# tfsasi.net
KiCad netlist of a schematic drawn in EAGLE
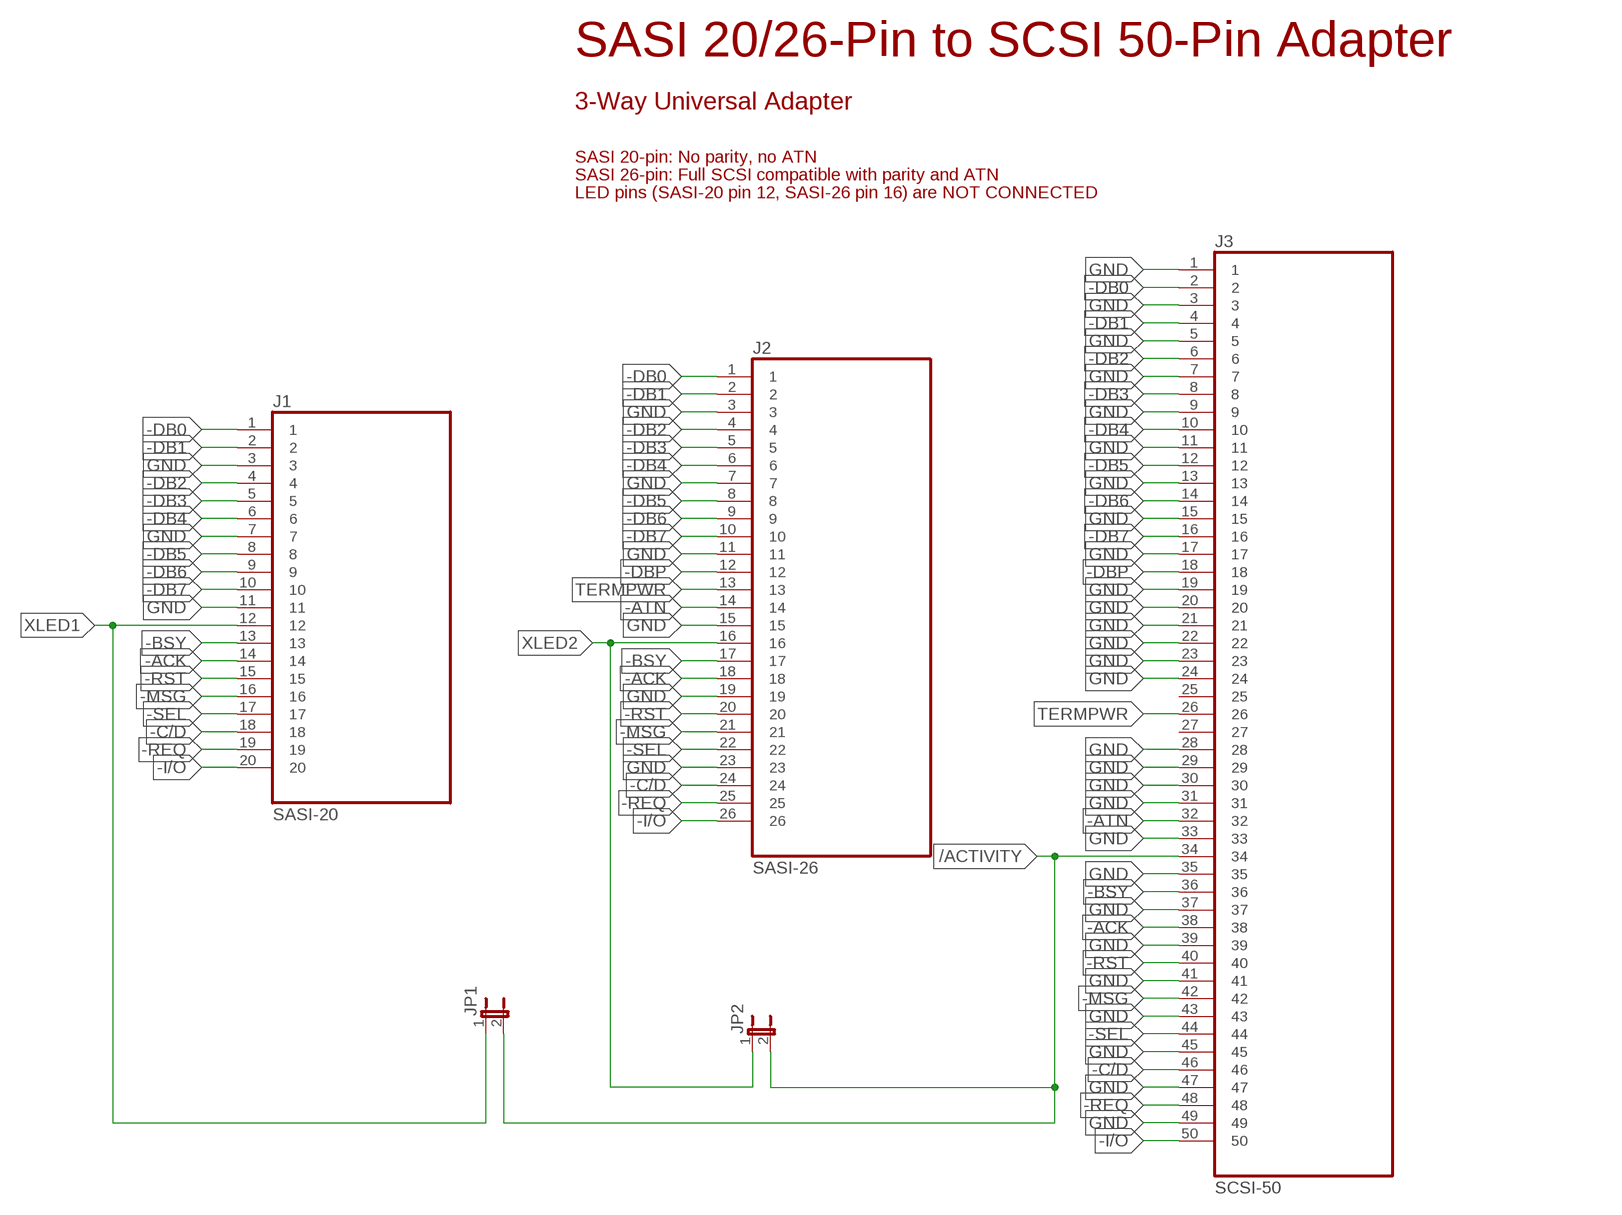
[diagram p0: schematic, sheet 1]

(export (version "E")
  (design (tool "Eeschema 10.0.6"))
  (components
    (comp (ref "J1")
      (value "SASI-20")
      (footprint "eagle-import:2X10")
      (libsource (lib "eagle-import") (part "SASI-20"))
    )
    (comp (ref "J2")
      (value "SASI-26")
      (footprint "eagle-import:2X13")
      (libsource (lib "eagle-import") (part "SASI-26"))
    )
    (comp (ref "J3")
      (value "SCSI-50")
      (footprint "eagle-import:2X25")
      (libsource (lib "eagle-import") (part "SCSI-50"))
    )
    (comp (ref "JP1")
      (value "JUMPER-2PTH")
      (footprint "eagle-import:1X02")
      (libsource (lib "eagle-import") (part "JUMPER-2PTH"))
    )
    (comp (ref "JP2")
      (value "JUMPER-2PTH")
      (footprint "eagle-import:1X02")
      (libsource (lib "eagle-import") (part "JUMPER-2PTH"))
    )
  )
  (nets
    (net (code "1") (name "-ACK") (class "Default")
      (node (ref "J1") (pin "14") (pinfunction "14_14") (pintype "passive"))
      (node (ref "J2") (pin "18") (pinfunction "18_18") (pintype "passive"))
      (node (ref "J3") (pin "38") (pinfunction "38_38") (pintype "passive"))
    )
    (net (code "2") (name "-ATN") (class "Default")
      (node (ref "J2") (pin "14") (pinfunction "14_14") (pintype "passive"))
      (node (ref "J3") (pin "32") (pinfunction "32_32") (pintype "passive"))
    )
    (net (code "3") (name "-BSY") (class "Default")
      (node (ref "J1") (pin "13") (pinfunction "13_13") (pintype "passive"))
      (node (ref "J2") (pin "17") (pinfunction "17_17") (pintype "passive"))
      (node (ref "J3") (pin "36") (pinfunction "36_36") (pintype "passive"))
    )
    (net (code "4") (name "-C{slash}D") (class "Default")
      (node (ref "J1") (pin "18") (pinfunction "18_18") (pintype "passive"))
      (node (ref "J2") (pin "24") (pinfunction "24_24") (pintype "passive"))
      (node (ref "J3") (pin "46") (pinfunction "46_46") (pintype "passive"))
    )
    (net (code "5") (name "-DB0") (class "Default")
      (node (ref "J1") (pin "1") (pinfunction "1_1") (pintype "passive"))
      (node (ref "J2") (pin "1") (pinfunction "1_1") (pintype "passive"))
      (node (ref "J3") (pin "2") (pinfunction "2_2") (pintype "passive"))
    )
    (net (code "6") (name "-DB1") (class "Default")
      (node (ref "J1") (pin "2") (pinfunction "2_2") (pintype "passive"))
      (node (ref "J2") (pin "2") (pinfunction "2_2") (pintype "passive"))
      (node (ref "J3") (pin "4") (pinfunction "4_4") (pintype "passive"))
    )
    (net (code "7") (name "-DB2") (class "Default")
      (node (ref "J1") (pin "4") (pinfunction "4_4") (pintype "passive"))
      (node (ref "J2") (pin "4") (pinfunction "4_4") (pintype "passive"))
      (node (ref "J3") (pin "6") (pinfunction "6_6") (pintype "passive"))
    )
    (net (code "8") (name "-DB3") (class "Default")
      (node (ref "J1") (pin "5") (pinfunction "5_5") (pintype "passive"))
      (node (ref "J2") (pin "5") (pinfunction "5_5") (pintype "passive"))
      (node (ref "J3") (pin "8") (pinfunction "8_8") (pintype "passive"))
    )
    (net (code "9") (name "-DB4") (class "Default")
      (node (ref "J1") (pin "6") (pinfunction "6_6") (pintype "passive"))
      (node (ref "J2") (pin "6") (pinfunction "6_6") (pintype "passive"))
      (node (ref "J3") (pin "10") (pinfunction "10_10") (pintype "passive"))
    )
    (net (code "10") (name "-DB5") (class "Default")
      (node (ref "J1") (pin "8") (pinfunction "8_8") (pintype "passive"))
      (node (ref "J2") (pin "8") (pinfunction "8_8") (pintype "passive"))
      (node (ref "J3") (pin "12") (pinfunction "12_12") (pintype "passive"))
    )
    (net (code "11") (name "-DB6") (class "Default")
      (node (ref "J1") (pin "9") (pinfunction "9_9") (pintype "passive"))
      (node (ref "J2") (pin "9") (pinfunction "9_9") (pintype "passive"))
      (node (ref "J3") (pin "14") (pinfunction "14_14") (pintype "passive"))
    )
    (net (code "12") (name "-DB7") (class "Default")
      (node (ref "J1") (pin "10") (pinfunction "10_10") (pintype "passive"))
      (node (ref "J2") (pin "10") (pinfunction "10_10") (pintype "passive"))
      (node (ref "J3") (pin "16") (pinfunction "16_16") (pintype "passive"))
    )
    (net (code "13") (name "-DBP") (class "Default")
      (node (ref "J2") (pin "12") (pinfunction "12_12") (pintype "passive"))
      (node (ref "J3") (pin "18") (pinfunction "18_18") (pintype "passive"))
    )
    (net (code "14") (name "-I{slash}O") (class "Default")
      (node (ref "J1") (pin "20") (pinfunction "20_20") (pintype "passive"))
      (node (ref "J2") (pin "26") (pinfunction "26_26") (pintype "passive"))
      (node (ref "J3") (pin "50") (pinfunction "50_50") (pintype "passive"))
    )
    (net (code "15") (name "-MSG") (class "Default")
      (node (ref "J1") (pin "16") (pinfunction "16_16") (pintype "passive"))
      (node (ref "J2") (pin "21") (pinfunction "21_21") (pintype "passive"))
      (node (ref "J3") (pin "42") (pinfunction "42_42") (pintype "passive"))
    )
    (net (code "16") (name "-REQ") (class "Default")
      (node (ref "J1") (pin "19") (pinfunction "19_19") (pintype "passive"))
      (node (ref "J2") (pin "25") (pinfunction "25_25") (pintype "passive"))
      (node (ref "J3") (pin "48") (pinfunction "48_48") (pintype "passive"))
    )
    (net (code "17") (name "-RST") (class "Default")
      (node (ref "J1") (pin "15") (pinfunction "15_15") (pintype "passive"))
      (node (ref "J2") (pin "20") (pinfunction "20_20") (pintype "passive"))
      (node (ref "J3") (pin "40") (pinfunction "40_40") (pintype "passive"))
    )
    (net (code "18") (name "-SEL") (class "Default")
      (node (ref "J1") (pin "17") (pinfunction "17_17") (pintype "passive"))
      (node (ref "J2") (pin "22") (pinfunction "22_22") (pintype "passive"))
      (node (ref "J3") (pin "44") (pinfunction "44_44") (pintype "passive"))
    )
    (net (code "19") (name "GND") (class "Default")
      (node (ref "J1") (pin "11") (pinfunction "11_11") (pintype "passive"))
      (node (ref "J1") (pin "3") (pinfunction "3_3") (pintype "passive"))
      (node (ref "J1") (pin "7") (pinfunction "7_7") (pintype "passive"))
      (node (ref "J2") (pin "11") (pinfunction "11_11") (pintype "passive"))
      (node (ref "J2") (pin "15") (pinfunction "15_15") (pintype "passive"))
      (node (ref "J2") (pin "19") (pinfunction "19_19") (pintype "passive"))
      (node (ref "J2") (pin "23") (pinfunction "23_23") (pintype "passive"))
      (node (ref "J2") (pin "3") (pinfunction "3_3") (pintype "passive"))
      (node (ref "J2") (pin "7") (pinfunction "7_7") (pintype "passive"))
      (node (ref "J3") (pin "1") (pinfunction "1_1") (pintype "passive"))
      (node (ref "J3") (pin "11") (pinfunction "11_11") (pintype "passive"))
      (node (ref "J3") (pin "13") (pinfunction "13_13") (pintype "passive"))
      (node (ref "J3") (pin "15") (pinfunction "15_15") (pintype "passive"))
      (node (ref "J3") (pin "17") (pinfunction "17_17") (pintype "passive"))
      (node (ref "J3") (pin "19") (pinfunction "19_19") (pintype "passive"))
      (node (ref "J3") (pin "20") (pinfunction "20_20") (pintype "passive"))
      (node (ref "J3") (pin "21") (pinfunction "21_21") (pintype "passive"))
      (node (ref "J3") (pin "22") (pinfunction "22_22") (pintype "passive"))
      (node (ref "J3") (pin "23") (pinfunction "23_23") (pintype "passive"))
      (node (ref "J3") (pin "24") (pinfunction "24_24") (pintype "passive"))
      (node (ref "J3") (pin "28") (pinfunction "28_28") (pintype "passive"))
      (node (ref "J3") (pin "29") (pinfunction "29_29") (pintype "passive"))
      (node (ref "J3") (pin "3") (pinfunction "3_3") (pintype "passive"))
      (node (ref "J3") (pin "30") (pinfunction "30_30") (pintype "passive"))
      (node (ref "J3") (pin "31") (pinfunction "31_31") (pintype "passive"))
      (node (ref "J3") (pin "33") (pinfunction "33_33") (pintype "passive"))
      (node (ref "J3") (pin "35") (pinfunction "35_35") (pintype "passive"))
      (node (ref "J3") (pin "37") (pinfunction "37_37") (pintype "passive"))
      (node (ref "J3") (pin "39") (pinfunction "39_39") (pintype "passive"))
      (node (ref "J3") (pin "41") (pinfunction "41_41") (pintype "passive"))
      (node (ref "J3") (pin "43") (pinfunction "43_43") (pintype "passive"))
      (node (ref "J3") (pin "45") (pinfunction "45_45") (pintype "passive"))
      (node (ref "J3") (pin "47") (pinfunction "47_47") (pintype "passive"))
      (node (ref "J3") (pin "49") (pinfunction "49_49") (pintype "passive"))
      (node (ref "J3") (pin "5") (pinfunction "5_5") (pintype "passive"))
      (node (ref "J3") (pin "7") (pinfunction "7_7") (pintype "passive"))
      (node (ref "J3") (pin "9") (pinfunction "9_9") (pintype "passive"))
    )
    (net (code "20") (name "TERMPWR") (class "Default")
      (node (ref "J2") (pin "13") (pinfunction "13_13") (pintype "passive"))
      (node (ref "J3") (pin "26") (pinfunction "26_26") (pintype "passive"))
    )
    (net (code "21") (name "XLED1") (class "Default")
      (node (ref "J1") (pin "12") (pinfunction "12_12") (pintype "passive"))
      (node (ref "JP1") (pin "1") (pinfunction "1_1") (pintype "passive"))
    )
    (net (code "22") (name "XLED2") (class "Default")
      (node (ref "J2") (pin "16") (pinfunction "16_16") (pintype "passive"))
      (node (ref "JP2") (pin "1") (pinfunction "1_1") (pintype "passive"))
    )
    (net (code "23") (name "unconnected-(J3-Pad25)") (class "Default")
      (node (ref "J3") (pin "25") (pinfunction "25_25") (pintype "passive"))
    )
    (net (code "24") (name "unconnected-(J3-Pad27)") (class "Default")
      (node (ref "J3") (pin "27") (pinfunction "27_27") (pintype "passive"))
    )
    (net (code "25") (name "{slash}ACTIVITY") (class "Default")
      (node (ref "J3") (pin "34") (pinfunction "34_34") (pintype "passive"))
      (node (ref "JP1") (pin "2") (pinfunction "2_2") (pintype "passive"))
      (node (ref "JP2") (pin "2") (pinfunction "2_2") (pintype "passive"))
    )
  )
)
